# esquema_v5.net
KiCad netlist of a schematic drawn in EAGLE
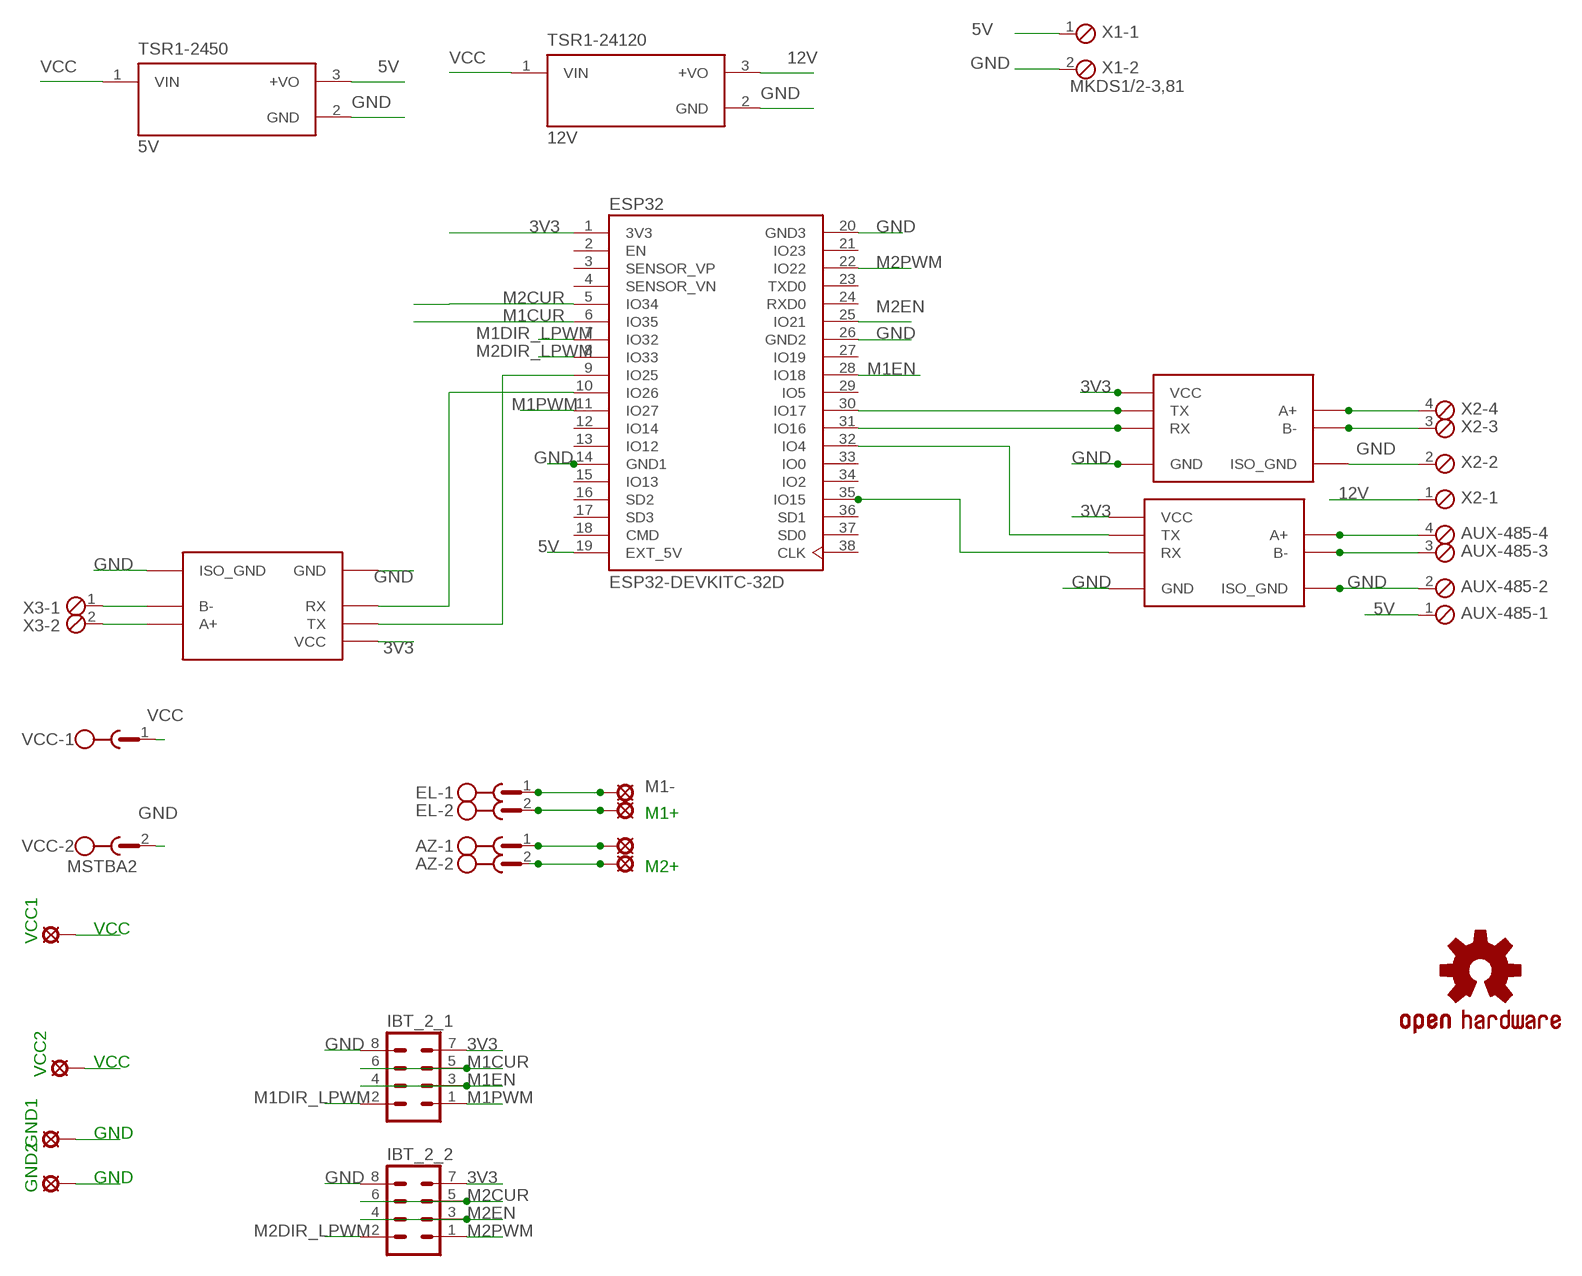
[diagram p0: schematic, sheet 1]

(export (version "E")
  (design (tool "Eeschema 10.0.6"))
  (components
    (comp (ref "AUX-485")
      (value "MKDS1/4-3,81")
      (footprint "eagle-import:4POL381")
      (libsource (lib "eagle-import") (part "MKDS1/4-3,81"))
    )
    (comp (ref "AZ")
      (value "MSTBA2")
      (footprint "eagle-import:MSTBA2")
      (fields (field (name "MF") "FARNELL") (field (name "MPN") "1757242"))
      (libsource (lib "eagle-import") (part "MSTBA2"))
    )
    (comp (ref "EL")
      (value "MSTBA2")
      (footprint "eagle-import:MSTBA2")
      (fields (field (name "MF") "FARNELL") (field (name "MPN") "1757242"))
      (libsource (lib "eagle-import") (part "MSTBA2"))
    )
    (comp (ref "ESP32")
      (value "ESP32-DEVKITC-32D")
      (footprint "eagle-import:MODULE_ESP32-DEVKITC-32D")
      (fields (field (name "MF") "Espressif Systems"))
      (libsource (lib "eagle-import") (part "ESP32-DEVKITC-32D"))
    )
    (comp (ref "GND1")
      (value "LSP10")
      (footprint "eagle-import:LSP10")
      (libsource (lib "eagle-import") (part "LSP10"))
    )
    (comp (ref "GND2")
      (value "LSP10")
      (footprint "eagle-import:LSP10")
      (libsource (lib "eagle-import") (part "LSP10"))
    )
    (comp (ref "IBT_2_1")
      (value "IBT_2_1")
      (footprint "eagle-import:MA04-2")
      (libsource (lib "eagle-import") (part "MA04-2"))
    )
    (comp (ref "IBT_2_2")
      (value "MA04-2")
      (footprint "eagle-import:MA04-2")
      (libsource (lib "eagle-import") (part "MA04-2"))
    )
    (comp (ref "LOGO1")
      (value "OSHW-LOGOMINI")
      (footprint "eagle-import:OSHW-LOGO-MINI")
      (libsource (lib "eagle-import") (part "OSHW-LOGOMINI"))
    )
    (comp (ref "M1+")
      (value "LSP10")
      (footprint "eagle-import:LSP10")
      (libsource (lib "eagle-import") (part "LSP10"))
    )
    (comp (ref "M1-")
      (value "LSP10")
      (footprint "eagle-import:LSP10")
      (libsource (lib "eagle-import") (part "LSP10"))
    )
    (comp (ref "M2")
      (value "LIMNOTECH_SMC_RS485")
      (footprint "eagle-import:LIMNOTECH_SMC_RS485")
      (libsource (lib "eagle-import") (part "LIMNOTECH_SMC_RS485"))
    )
    (comp (ref "M2+")
      (value "LSP10")
      (footprint "eagle-import:LSP10")
      (libsource (lib "eagle-import") (part "LSP10"))
    )
    (comp (ref "M2-")
      (value "M2-")
      (footprint "eagle-import:LSP10")
      (libsource (lib "eagle-import") (part "LSP10"))
    )
    (comp (ref "M3")
      (value "LIMNOTECH_SMC_RS485")
      (footprint "eagle-import:LIMNOTECH_SMC_RS485")
      (libsource (lib "eagle-import") (part "LIMNOTECH_SMC_RS485"))
    )
    (comp (ref "M4")
      (value "LIMNOTECH_SMC_RS485")
      (footprint "eagle-import:LIMNOTECH_SMC_RS485")
      (libsource (lib "eagle-import") (part "LIMNOTECH_SMC_RS485"))
    )
    (comp (ref "TSR1-2450")
      (value "5V")
      (footprint "eagle-import:CONV_K7803-500R3")
      (fields (field (name "MF") "Mornsun America, LLC") (field (name "MP") "K7803-500R3"))
      (libsource (lib "eagle-import") (part "K7803-500R3"))
    )
    (comp (ref "TSR1-24120")
      (value "12V")
      (footprint "eagle-import:CONV_K7803-500R3")
      (fields (field (name "MF") "Mornsun America, LLC") (field (name "MP") "K7803-500R3"))
      (libsource (lib "eagle-import") (part "K7803-500R3"))
    )
    (comp (ref "VCC")
      (value "MSTBA2")
      (footprint "eagle-import:MSTBA2")
      (fields (field (name "MF") "FARNELL") (field (name "MPN") "1757242"))
      (libsource (lib "eagle-import") (part "MSTBA2"))
    )
    (comp (ref "VCC1")
      (value "LSP10")
      (footprint "eagle-import:LSP10")
      (libsource (lib "eagle-import") (part "LSP10"))
    )
    (comp (ref "VCC2")
      (value "LSP10")
      (footprint "eagle-import:LSP10")
      (libsource (lib "eagle-import") (part "LSP10"))
    )
    (comp (ref "X1")
      (value "MKDS1/2-3,81")
      (footprint "eagle-import:2POL381")
      (libsource (lib "eagle-import") (part "MKDS1/2-3,81"))
    )
    (comp (ref "X2")
      (value "MKDS1/4-3,81")
      (footprint "eagle-import:4POL381")
      (libsource (lib "eagle-import") (part "MKDS1/4-3,81"))
    )
    (comp (ref "X3")
      (value "MKDS1/2-3,81")
      (footprint "eagle-import:2POL381")
      (libsource (lib "eagle-import") (part "MKDS1/2-3,81"))
    )
  )
  (nets
    (net (code "1") (name "/3V3") (class "Default")
      (node (ref "ESP32") (pin "1") (pinfunction "3V3_1") (pintype "power_in"))
      (node (ref "IBT_2_1") (pin "7") (pinfunction "7_7") (pintype "passive"))
      (node (ref "IBT_2_2") (pin "7") (pinfunction "7_7") (pintype "passive"))
      (node (ref "M2") (pin "VCC") (pinfunction "VCC_VCC") (pintype "bidirectional"))
      (node (ref "M3") (pin "VCC") (pinfunction "VCC_VCC") (pintype "bidirectional"))
      (node (ref "M4") (pin "VCC") (pinfunction "VCC_VCC") (pintype "bidirectional"))
    )
    (net (code "2") (name "/5V") (class "Default")
      (node (ref "AUX-485") (pin "1") (pinfunction "1_1") (pintype "passive"))
      (node (ref "ESP32") (pin "19") (pinfunction "EXT_5V_19") (pintype "power_in"))
      (node (ref "TSR1-2450") (pin "3") (pinfunction "+VO_3") (pintype "output"))
      (node (ref "X1") (pin "1") (pinfunction "1_1") (pintype "passive"))
    )
    (net (code "3") (name "/12V") (class "Default")
      (node (ref "TSR1-24120") (pin "3") (pinfunction "+VO_3") (pintype "output"))
      (node (ref "X2") (pin "1") (pinfunction "1_1") (pintype "passive"))
    )
    (net (code "4") (name "/GND") (class "Default")
      (node (ref "AUX-485") (pin "2") (pinfunction "1_2") (pintype "passive"))
      (node (ref "ESP32") (pin "14") (pinfunction "GND1_14") (pintype "power_in"))
      (node (ref "ESP32") (pin "20") (pinfunction "GND3_20") (pintype "power_in"))
      (node (ref "ESP32") (pin "26") (pinfunction "GND2_26") (pintype "power_in"))
      (node (ref "GND1") (pin "MP") (pinfunction "MP_MP") (pintype "passive"))
      (node (ref "GND2") (pin "MP") (pinfunction "MP_MP") (pintype "passive"))
      (node (ref "IBT_2_1") (pin "8") (pinfunction "8_8") (pintype "passive"))
      (node (ref "IBT_2_2") (pin "8") (pinfunction "8_8") (pintype "passive"))
      (node (ref "M2") (pin "GND") (pinfunction "GND_GND") (pintype "bidirectional"))
      (node (ref "M2") (pin "GND_ISO") (pinfunction "ISO_GND_GND_ISO") (pintype "bidirectional"))
      (node (ref "M3") (pin "GND") (pinfunction "GND_GND") (pintype "bidirectional"))
      (node (ref "M3") (pin "GND_ISO") (pinfunction "ISO_GND_GND_ISO") (pintype "bidirectional"))
      (node (ref "M4") (pin "GND") (pinfunction "GND_GND") (pintype "bidirectional"))
      (node (ref "M4") (pin "GND_ISO") (pinfunction "ISO_GND_GND_ISO") (pintype "bidirectional"))
      (node (ref "TSR1-24120") (pin "2") (pinfunction "GND_2") (pintype "power_in"))
      (node (ref "TSR1-2450") (pin "2") (pinfunction "GND_2") (pintype "power_in"))
      (node (ref "VCC") (pin "2") (pinfunction "1_2") (pintype "passive"))
      (node (ref "X1") (pin "2") (pinfunction "1_2") (pintype "passive"))
      (node (ref "X2") (pin "2") (pinfunction "1_2") (pintype "passive"))
    )
    (net (code "5") (name "/M1+") (class "Default")
      (node (ref "EL") (pin "2") (pinfunction "1_2") (pintype "passive"))
      (node (ref "M1+") (pin "MP") (pinfunction "MP_MP") (pintype "passive"))
    )
    (net (code "6") (name "/M1-") (class "Default")
      (node (ref "EL") (pin "1") (pinfunction "1_1") (pintype "passive"))
      (node (ref "M1-") (pin "MP") (pinfunction "MP_MP") (pintype "passive"))
    )
    (net (code "7") (name "/M1CUR") (class "Default")
      (node (ref "ESP32") (pin "6") (pinfunction "IO35_6") (pintype "bidirectional"))
      (node (ref "IBT_2_1") (pin "5") (pinfunction "5_5") (pintype "passive"))
      (node (ref "IBT_2_1") (pin "6") (pinfunction "6_6") (pintype "passive"))
    )
    (net (code "8") (name "/M1DIR_LPWM") (class "Default")
      (node (ref "ESP32") (pin "7") (pinfunction "IO32_7") (pintype "bidirectional"))
      (node (ref "IBT_2_1") (pin "2") (pinfunction "2_2") (pintype "passive"))
    )
    (net (code "9") (name "/M1EN") (class "Default")
      (node (ref "ESP32") (pin "28") (pinfunction "IO18_28") (pintype "bidirectional"))
      (node (ref "IBT_2_1") (pin "3") (pinfunction "3_3") (pintype "passive"))
      (node (ref "IBT_2_1") (pin "4") (pinfunction "4_4") (pintype "passive"))
    )
    (net (code "10") (name "/M1PWM") (class "Default")
      (node (ref "ESP32") (pin "11") (pinfunction "IO27_11") (pintype "bidirectional"))
      (node (ref "IBT_2_1") (pin "1") (pinfunction "1_1") (pintype "passive"))
    )
    (net (code "11") (name "/M2+") (class "Default")
      (node (ref "AZ") (pin "2") (pinfunction "1_2") (pintype "passive"))
      (node (ref "M2+") (pin "MP") (pinfunction "MP_MP") (pintype "passive"))
    )
    (net (code "12") (name "/M2CUR") (class "Default")
      (node (ref "ESP32") (pin "5") (pinfunction "IO34_5") (pintype "bidirectional"))
      (node (ref "IBT_2_2") (pin "5") (pinfunction "5_5") (pintype "passive"))
      (node (ref "IBT_2_2") (pin "6") (pinfunction "6_6") (pintype "passive"))
    )
    (net (code "13") (name "/M2DIR_LPWM") (class "Default")
      (node (ref "ESP32") (pin "8") (pinfunction "IO33_8") (pintype "bidirectional"))
      (node (ref "IBT_2_2") (pin "2") (pinfunction "2_2") (pintype "passive"))
    )
    (net (code "14") (name "/M2EN") (class "Default")
      (node (ref "ESP32") (pin "25") (pinfunction "IO21_25") (pintype "bidirectional"))
      (node (ref "IBT_2_2") (pin "3") (pinfunction "3_3") (pintype "passive"))
      (node (ref "IBT_2_2") (pin "4") (pinfunction "4_4") (pintype "passive"))
    )
    (net (code "15") (name "/M2PWM") (class "Default")
      (node (ref "ESP32") (pin "22") (pinfunction "IO22_22") (pintype "bidirectional"))
      (node (ref "IBT_2_2") (pin "1") (pinfunction "1_1") (pintype "passive"))
    )
    (net (code "16") (name "/VCC") (class "Default")
      (node (ref "TSR1-24120") (pin "1") (pinfunction "VIN_1") (pintype "input"))
      (node (ref "TSR1-2450") (pin "1") (pinfunction "VIN_1") (pintype "input"))
      (node (ref "VCC") (pin "1") (pinfunction "1_1") (pintype "passive"))
      (node (ref "VCC1") (pin "MP") (pinfunction "MP_MP") (pintype "passive"))
      (node (ref "VCC2") (pin "MP") (pinfunction "MP_MP") (pintype "passive"))
    )
    (net (code "17") (name "Net-(AUX-485C-1)") (class "Default")
      (node (ref "AUX-485") (pin "3") (pinfunction "1_3") (pintype "passive"))
      (node (ref "M2") (pin "B-") (pinfunction "B-_B-") (pintype "bidirectional"))
    )
    (net (code "18") (name "Net-(AUX-485D-1)") (class "Default")
      (node (ref "AUX-485") (pin "4") (pinfunction "1_4") (pintype "passive"))
      (node (ref "M2") (pin "A+") (pinfunction "A+_A+") (pintype "bidirectional"))
    )
    (net (code "19") (name "Net-(AZ-Pad1)") (class "Default")
      (node (ref "AZ") (pin "1") (pinfunction "1_1") (pintype "passive"))
      (node (ref "M2-") (pin "MP") (pinfunction "MP_MP") (pintype "passive"))
    )
    (net (code "20") (name "Net-(ESP32-IO4)") (class "Default")
      (node (ref "ESP32") (pin "32") (pinfunction "IO4_32") (pintype "bidirectional"))
      (node (ref "M2") (pin "TX") (pinfunction "TX_TX") (pintype "bidirectional"))
    )
    (net (code "21") (name "Net-(ESP32-IO15)") (class "Default")
      (node (ref "ESP32") (pin "35") (pinfunction "IO15_35") (pintype "bidirectional"))
      (node (ref "M2") (pin "RX") (pinfunction "RX_RX") (pintype "bidirectional"))
    )
    (net (code "22") (name "Net-(ESP32-IO16)") (class "Default")
      (node (ref "ESP32") (pin "31") (pinfunction "IO16_31") (pintype "bidirectional"))
      (node (ref "M4") (pin "RX") (pinfunction "RX_RX") (pintype "bidirectional"))
    )
    (net (code "23") (name "Net-(ESP32-IO17)") (class "Default")
      (node (ref "ESP32") (pin "30") (pinfunction "IO17_30") (pintype "bidirectional"))
      (node (ref "M4") (pin "TX") (pinfunction "TX_TX") (pintype "bidirectional"))
    )
    (net (code "24") (name "Net-(ESP32-IO25)") (class "Default")
      (node (ref "ESP32") (pin "9") (pinfunction "IO25_9") (pintype "bidirectional"))
      (node (ref "M3") (pin "TX") (pinfunction "TX_TX") (pintype "bidirectional"))
    )
    (net (code "25") (name "Net-(ESP32-IO26)") (class "Default")
      (node (ref "ESP32") (pin "10") (pinfunction "IO26_10") (pintype "bidirectional"))
      (node (ref "M3") (pin "RX") (pinfunction "RX_RX") (pintype "bidirectional"))
    )
    (net (code "26") (name "Net-(M3-PadB-)") (class "Default")
      (node (ref "M3") (pin "B-") (pinfunction "B-_B-") (pintype "bidirectional"))
      (node (ref "X3") (pin "1") (pinfunction "1_1") (pintype "passive"))
    )
    (net (code "27") (name "Net-(X2C-1)") (class "Default")
      (node (ref "M4") (pin "B-") (pinfunction "B-_B-") (pintype "bidirectional"))
      (node (ref "X2") (pin "3") (pinfunction "1_3") (pintype "passive"))
    )
    (net (code "28") (name "Net-(X2D-1)") (class "Default")
      (node (ref "M4") (pin "A+") (pinfunction "A+_A+") (pintype "bidirectional"))
      (node (ref "X2") (pin "4") (pinfunction "1_4") (pintype "passive"))
    )
    (net (code "29") (name "Net-(X3B-1)") (class "Default")
      (node (ref "M3") (pin "A+") (pinfunction "A+_A+") (pintype "bidirectional"))
      (node (ref "X3") (pin "2") (pinfunction "1_2") (pintype "passive"))
    )
    (net (code "30") (name "unconnected-(ESP32-CLK-Pad38)") (class "Default")
      (node (ref "ESP32") (pin "38") (pinfunction "CLK_38") (pintype "input"))
    )
    (net (code "31") (name "unconnected-(ESP32-CMD-Pad18)") (class "Default")
      (node (ref "ESP32") (pin "18") (pinfunction "CMD_18") (pintype "bidirectional"))
    )
    (net (code "32") (name "unconnected-(ESP32-EN-Pad2)") (class "Default")
      (node (ref "ESP32") (pin "2") (pinfunction "EN_2") (pintype "input"))
    )
    (net (code "33") (name "unconnected-(ESP32-IO0-Pad33)") (class "Default")
      (node (ref "ESP32") (pin "33") (pinfunction "IO0_33") (pintype "bidirectional"))
    )
    (net (code "34") (name "unconnected-(ESP32-IO2-Pad34)") (class "Default")
      (node (ref "ESP32") (pin "34") (pinfunction "IO2_34") (pintype "bidirectional"))
    )
    (net (code "35") (name "unconnected-(ESP32-IO5-Pad29)") (class "Default")
      (node (ref "ESP32") (pin "29") (pinfunction "IO5_29") (pintype "bidirectional"))
    )
    (net (code "36") (name "unconnected-(ESP32-IO12-Pad13)") (class "Default")
      (node (ref "ESP32") (pin "13") (pinfunction "IO12_13") (pintype "bidirectional"))
    )
    (net (code "37") (name "unconnected-(ESP32-IO13-Pad15)") (class "Default")
      (node (ref "ESP32") (pin "15") (pinfunction "IO13_15") (pintype "bidirectional"))
    )
    (net (code "38") (name "unconnected-(ESP32-IO14-Pad12)") (class "Default")
      (node (ref "ESP32") (pin "12") (pinfunction "IO14_12") (pintype "bidirectional"))
    )
    (net (code "39") (name "unconnected-(ESP32-IO19-Pad27)") (class "Default")
      (node (ref "ESP32") (pin "27") (pinfunction "IO19_27") (pintype "bidirectional"))
    )
    (net (code "40") (name "unconnected-(ESP32-IO23-Pad21)") (class "Default")
      (node (ref "ESP32") (pin "21") (pinfunction "IO23_21") (pintype "bidirectional"))
    )
    (net (code "41") (name "unconnected-(ESP32-RXD0-Pad24)") (class "Default")
      (node (ref "ESP32") (pin "24") (pinfunction "RXD0_24") (pintype "input"))
    )
    (net (code "42") (name "unconnected-(ESP32-SD0-Pad37)") (class "Default")
      (node (ref "ESP32") (pin "37") (pinfunction "SD0_37") (pintype "bidirectional"))
    )
    (net (code "43") (name "unconnected-(ESP32-SD1-Pad36)") (class "Default")
      (node (ref "ESP32") (pin "36") (pinfunction "SD1_36") (pintype "bidirectional"))
    )
    (net (code "44") (name "unconnected-(ESP32-SD2-Pad16)") (class "Default")
      (node (ref "ESP32") (pin "16") (pinfunction "SD2_16") (pintype "bidirectional"))
    )
    (net (code "45") (name "unconnected-(ESP32-SD3-Pad17)") (class "Default")
      (node (ref "ESP32") (pin "17") (pinfunction "SD3_17") (pintype "bidirectional"))
    )
    (net (code "46") (name "unconnected-(ESP32-SENSOR_VN-Pad4)") (class "Default")
      (node (ref "ESP32") (pin "4") (pinfunction "SENSOR_VN_4") (pintype "input"))
    )
    (net (code "47") (name "unconnected-(ESP32-SENSOR_VP-Pad3)") (class "Default")
      (node (ref "ESP32") (pin "3") (pinfunction "SENSOR_VP_3") (pintype "input"))
    )
    (net (code "48") (name "unconnected-(ESP32-TXD0-Pad23)") (class "Default")
      (node (ref "ESP32") (pin "23") (pinfunction "TXD0_23") (pintype "output"))
    )
  )
)
